# mini64se-v1_0_9-F4-2s.net
KiCad netlist of a schematic drawn in EAGLE
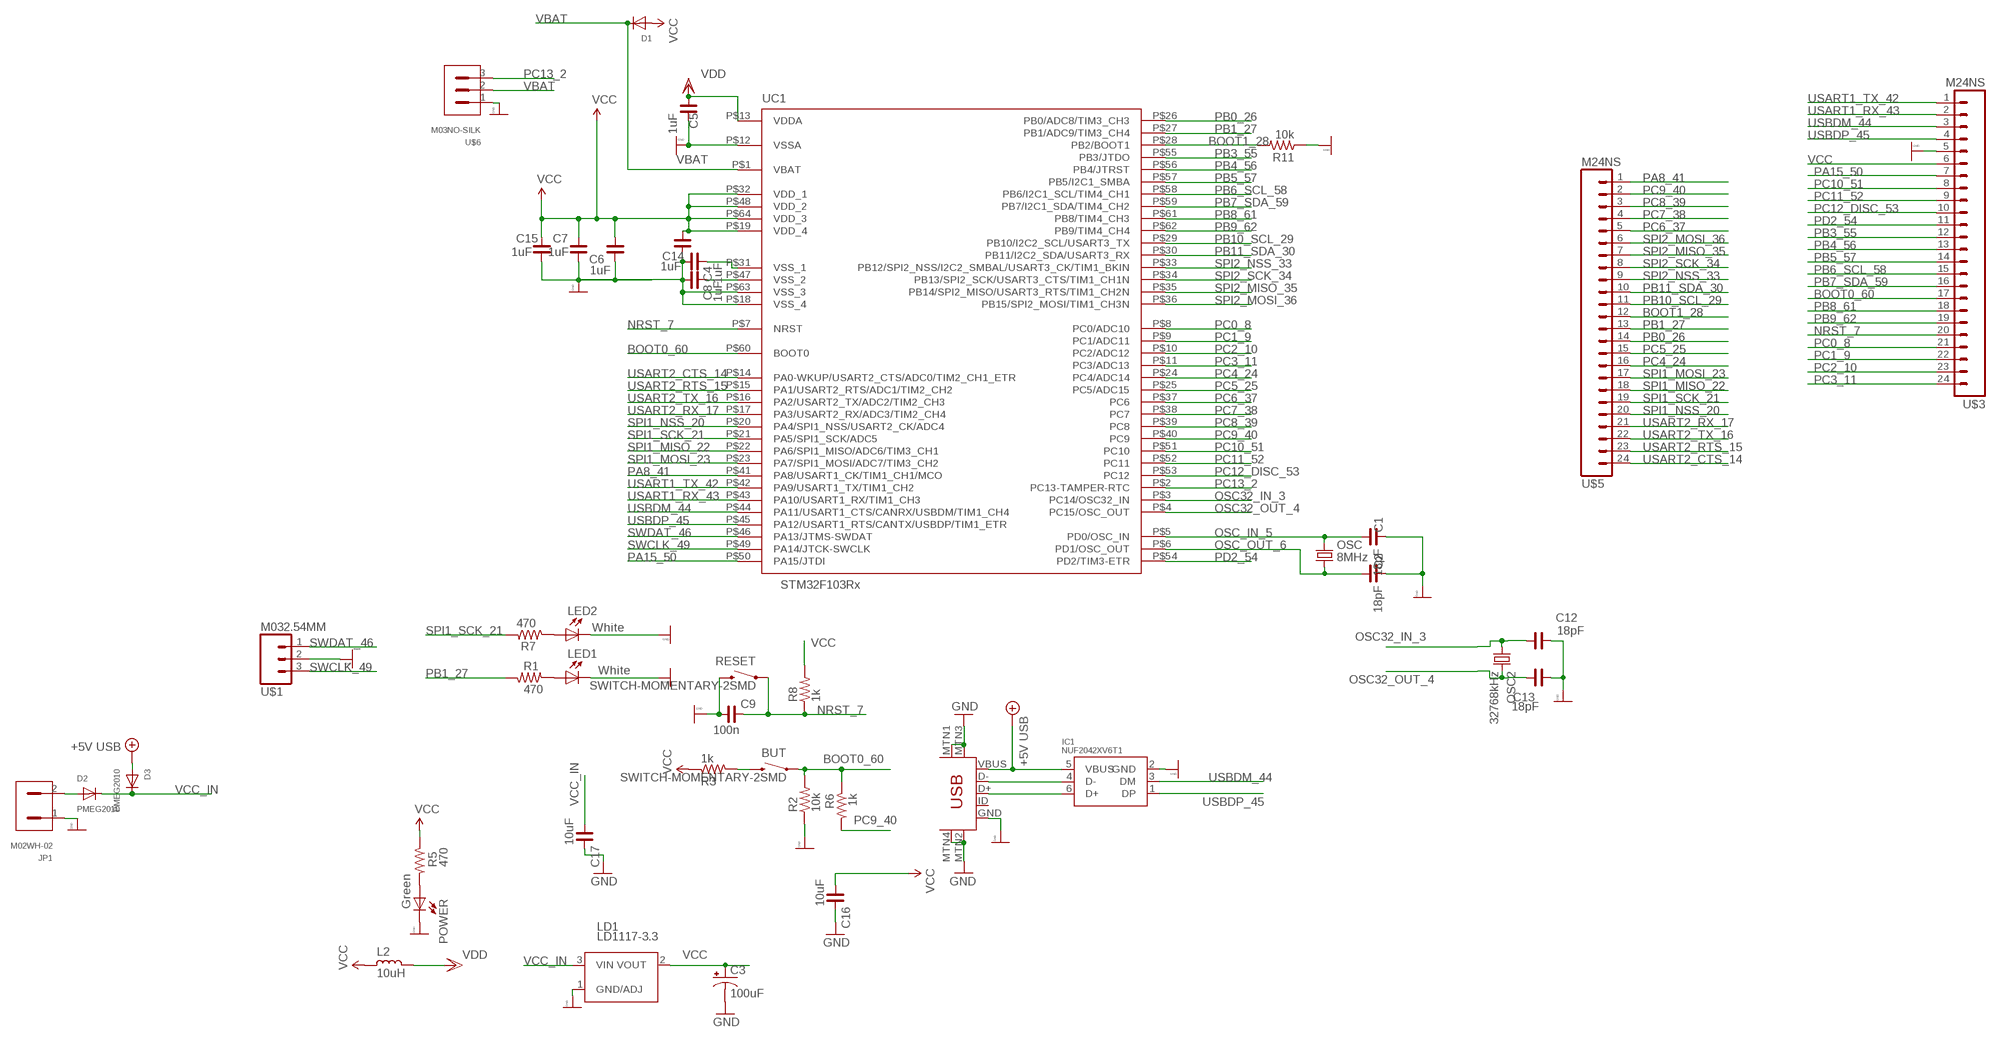
[diagram p0: schematic, sheet 1]

(export (version "E")
  (design (tool "Eeschema 10.0.6"))
  (components
    (comp (ref "BUT")
      (value "SWITCH-MOMENTARY-2SMD")
      (footprint "eagle-import:TACTILE_SWITCH_SMD")
      (libsource (lib "eagle-import") (part "SWITCH-MOMENTARY-2SMD"))
    )
    (comp (ref "C1")
      (value "18pF")
      (footprint "eagle-import:C0603")
      (libsource (lib "eagle-import") (part "C_0603"))
    )
    (comp (ref "C2")
      (value "18pF")
      (footprint "eagle-import:C0603")
      (libsource (lib "eagle-import") (part "C_0603"))
    )
    (comp (ref "C3")
      (value "100uF")
      (footprint "eagle-import:PANASONIC_C")
      (libsource (lib "eagle-import") (part "CAP_POLC"))
    )
    (comp (ref "C4")
      (value "1uF")
      (footprint "eagle-import:C0603")
      (libsource (lib "eagle-import") (part "C_0603"))
    )
    (comp (ref "C5")
      (value "1uF")
      (footprint "eagle-import:C0603")
      (libsource (lib "eagle-import") (part "C_0603"))
    )
    (comp (ref "C6")
      (value "1uF")
      (footprint "eagle-import:C0603")
      (libsource (lib "eagle-import") (part "C_0603"))
    )
    (comp (ref "C7")
      (value "1uF")
      (footprint "eagle-import:C0603")
      (libsource (lib "eagle-import") (part "C_0603"))
    )
    (comp (ref "C8")
      (value "1uF")
      (footprint "eagle-import:C0603")
      (libsource (lib "eagle-import") (part "C_0603"))
    )
    (comp (ref "C9")
      (value "100n")
      (footprint "eagle-import:C0603")
      (libsource (lib "eagle-import") (part "C_0603"))
    )
    (comp (ref "C12")
      (value "18pF")
      (footprint "eagle-import:C0603")
      (libsource (lib "eagle-import") (part "C_0603"))
    )
    (comp (ref "C13")
      (value "18pF")
      (footprint "eagle-import:C0603")
      (libsource (lib "eagle-import") (part "C_0603"))
    )
    (comp (ref "C14")
      (value "1uF")
      (footprint "eagle-import:C0603")
      (libsource (lib "eagle-import") (part "C_0603"))
    )
    (comp (ref "C15")
      (value "1uF")
      (footprint "eagle-import:C0603")
      (libsource (lib "eagle-import") (part "C_0603"))
    )
    (comp (ref "C16")
      (value "10uF")
      (footprint "eagle-import:C0805")
      (libsource (lib "eagle-import") (part "C_0805"))
    )
    (comp (ref "C17")
      (value "10uF")
      (footprint "eagle-import:C0805")
      (libsource (lib "eagle-import") (part "C_0805"))
    )
    (comp (ref "D1")
      (value "DIODESOD-123")
      (footprint "eagle-import:SOD-123")
      (libsource (lib "eagle-import") (part "DIODESOD-123"))
    )
    (comp (ref "D2")
      (value "PMEG2010")
      (footprint "eagle-import:SOD-123")
      (libsource (lib "eagle-import") (part "DIODESOD-123"))
    )
    (comp (ref "D3")
      (value "PMEG2010")
      (footprint "eagle-import:SOD-123")
      (libsource (lib "eagle-import") (part "DIODESOD-123"))
    )
    (comp (ref "IC1")
      (value "NUF2042XV6T1")
      (footprint "eagle-import:SOT-563")
      (libsource (lib "eagle-import") (part "NUF2042XV6T1"))
    )
    (comp (ref "JP1")
      (value "M02WH-02")
      (footprint "eagle-import:WH-02R")
      (libsource (lib "eagle-import") (part "M02WH-02"))
    )
    (comp (ref "L2")
      (value "10uH")
      (footprint "eagle-import:PM0603")
      (libsource (lib "eagle-import") (part "L_PM0603"))
    )
    (comp (ref "LD1")
      (value "LD1117-3.3")
      (footprint "eagle-import:SOT223")
      (libsource (lib "eagle-import") (part "LD1117SOT223"))
    )
    (comp (ref "LED1")
      (value "White")
      (footprint "eagle-import:CHIPLED_1206")
      (libsource (lib "eagle-import") (part "LEDCHIPLED_1206"))
    )
    (comp (ref "LED2")
      (value "White")
      (footprint "eagle-import:CHIPLED_1206")
      (libsource (lib "eagle-import") (part "LEDCHIPLED_1206"))
    )
    (comp (ref "OSC")
      (value "8MHz")
      (footprint "eagle-import:HC49U-V")
      (libsource (lib "eagle-import") (part "CRYSTALHC49UV"))
    )
    (comp (ref "OSC2")
      (value "32768kHz")
      (footprint "eagle-import:TC26H-M")
      (libsource (lib "eagle-import") (part "CRYSTALTC26HM"))
    )
    (comp (ref "POWER")
      (value "Green")
      (footprint "eagle-import:CHIP-LED0805")
      (libsource (lib "eagle-import") (part "LEDCHIP-LED0805"))
    )
    (comp (ref "R1")
      (value "470")
      (footprint "eagle-import:R0603")
      (libsource (lib "eagle-import") (part "R_0603"))
    )
    (comp (ref "R2")
      (value "10k")
      (footprint "eagle-import:R0603")
      (libsource (lib "eagle-import") (part "R_0603"))
    )
    (comp (ref "R3")
      (value "1k")
      (footprint "eagle-import:R0603")
      (libsource (lib "eagle-import") (part "R_0603"))
    )
    (comp (ref "R5")
      (value "470")
      (footprint "eagle-import:R0603")
      (libsource (lib "eagle-import") (part "R_0603"))
    )
    (comp (ref "R6")
      (value "1k")
      (footprint "eagle-import:R0603")
      (libsource (lib "eagle-import") (part "R_0603"))
    )
    (comp (ref "R7")
      (value "470")
      (footprint "eagle-import:R0603")
      (libsource (lib "eagle-import") (part "R_0603"))
    )
    (comp (ref "R8")
      (value "1k")
      (footprint "eagle-import:R0603")
      (libsource (lib "eagle-import") (part "R_0603"))
    )
    (comp (ref "R11")
      (value "10k")
      (footprint "eagle-import:R0603")
      (libsource (lib "eagle-import") (part "R_0603"))
    )
    (comp (ref "RESET")
      (value "SWITCH-MOMENTARY-2SMD")
      (footprint "eagle-import:TACTILE_SWITCH_SMD")
      (libsource (lib "eagle-import") (part "SWITCH-MOMENTARY-2SMD"))
    )
    (comp (ref "U$1")
      (value "M032.54MM")
      (footprint "eagle-import:1X03_NO_SILK")
      (libsource (lib "eagle-import") (part "M031X03_NO_SILK"))
    )
    (comp (ref "U$3")
      (value "M24NS")
      (footprint "eagle-import:1X24_NO_SILK")
      (libsource (lib "eagle-import") (part "M24NS"))
    )
    (comp (ref "U$5")
      (value "M24NS")
      (footprint "eagle-import:1X24_NO_SILK")
      (libsource (lib "eagle-import") (part "M24NS"))
    )
    (comp (ref "U$6")
      (value "M03NO-SILK")
      (footprint "eagle-import:1X03_NO_SILK")
      (libsource (lib "eagle-import") (part "M03NO-SILK"))
    )
    (comp (ref "UC1")
      (value "STM32F103Rx")
      (footprint "eagle-import:TQFP-10X10-64")
      (libsource (lib "eagle-import") (part "STM32F103"))
    )
    (comp (ref "USB")
      (value "USB-MINIB-5PIN")
      (footprint "eagle-import:USB-MINIB")
      (libsource (lib "eagle-import") (part "USB-MINIB-5PIN"))
    )
  )
  (nets
    (net (code "1") (name "+5V USB") (class "Default")
      (node (ref "D3") (pin "A") (pinfunction "A_A") (pintype "passive"))
      (node (ref "IC1") (pin "5") (pinfunction "VBUS_5") (pintype "bidirectional"))
      (node (ref "USB") (pin "VBUS") (pinfunction "VBUS_VBUS") (pintype "bidirectional"))
    )
    (net (code "2") (name "/BOOT0_60") (class "Default")
      (node (ref "BUT") (pin "1") (pinfunction "1_1") (pintype "passive"))
      (node (ref "R2") (pin "2") (pinfunction "2_2") (pintype "passive"))
      (node (ref "R6") (pin "1") (pinfunction "1_1") (pintype "passive"))
      (node (ref "U$3") (pin "17") (pinfunction "18_17") (pintype "passive"))
      (node (ref "UC1") (pin "P$60") (pinfunction "BOOT0_P$60") (pintype "bidirectional"))
    )
    (net (code "3") (name "/BOOT1_28") (class "Default")
      (node (ref "R11") (pin "2") (pinfunction "2_2") (pintype "passive"))
      (node (ref "U$5") (pin "12") (pinfunction "13_12") (pintype "passive"))
      (node (ref "UC1") (pin "P$28") (pinfunction "PB2/BOOT1_P$28") (pintype "bidirectional"))
    )
    (net (code "4") (name "/NRST_7") (class "Default")
      (node (ref "C9") (pin "2") (pinfunction "2_2") (pintype "passive"))
      (node (ref "R8") (pin "1") (pinfunction "1_1") (pintype "passive"))
      (node (ref "RESET") (pin "1") (pinfunction "1_1") (pintype "passive"))
      (node (ref "U$3") (pin "20") (pinfunction "21_20") (pintype "passive"))
      (node (ref "UC1") (pin "P$7") (pinfunction "NRST_P$7") (pintype "bidirectional"))
    )
    (net (code "5") (name "/OSC32_IN_3") (class "Default")
      (node (ref "C12") (pin "2") (pinfunction "2_2") (pintype "passive"))
      (node (ref "OSC2") (pin "1") (pinfunction "1_1") (pintype "passive"))
      (node (ref "UC1") (pin "P$3") (pinfunction "PC14/OSC32_IN_P$3") (pintype "bidirectional"))
    )
    (net (code "6") (name "/OSC32_OUT_4") (class "Default")
      (node (ref "C13") (pin "2") (pinfunction "2_2") (pintype "passive"))
      (node (ref "OSC2") (pin "2") (pinfunction "2_2") (pintype "passive"))
      (node (ref "UC1") (pin "P$4") (pinfunction "PC15/OSC_OUT_P$4") (pintype "bidirectional"))
    )
    (net (code "7") (name "/OSC_IN_5") (class "Default")
      (node (ref "C1") (pin "2") (pinfunction "2_2") (pintype "passive"))
      (node (ref "OSC") (pin "2") (pinfunction "2_2") (pintype "passive"))
      (node (ref "UC1") (pin "P$5") (pinfunction "PD0/OSC_IN_P$5") (pintype "bidirectional"))
    )
    (net (code "8") (name "/OSC_OUT_6") (class "Default")
      (node (ref "C2") (pin "2") (pinfunction "2_2") (pintype "passive"))
      (node (ref "OSC") (pin "1") (pinfunction "1_1") (pintype "passive"))
      (node (ref "UC1") (pin "P$6") (pinfunction "PD1/OSC_OUT_P$6") (pintype "bidirectional"))
    )
    (net (code "9") (name "/PA8_41") (class "Default")
      (node (ref "U$5") (pin "1") (pinfunction "2_1") (pintype "passive"))
      (node (ref "UC1") (pin "P$41") (pinfunction "PA8/USART1_CK/TIM1_CH1/MCO_P$41") (pintype "bidirectional"))
    )
    (net (code "10") (name "/PA15_50") (class "Default")
      (node (ref "U$3") (pin "7") (pinfunction "8_7") (pintype "passive"))
      (node (ref "UC1") (pin "P$50") (pinfunction "PA15/JTDI_P$50") (pintype "bidirectional"))
    )
    (net (code "11") (name "/PB0_26") (class "Default")
      (node (ref "U$5") (pin "14") (pinfunction "15_14") (pintype "passive"))
      (node (ref "UC1") (pin "P$26") (pinfunction "PB0/ADC8/TIM3_CH3_P$26") (pintype "bidirectional"))
    )
    (net (code "12") (name "/PB1_27") (class "Default")
      (node (ref "R1") (pin "2") (pinfunction "2_2") (pintype "passive"))
      (node (ref "U$5") (pin "13") (pinfunction "14_13") (pintype "passive"))
      (node (ref "UC1") (pin "P$27") (pinfunction "PB1/ADC9/TIM3_CH4_P$27") (pintype "bidirectional"))
    )
    (net (code "13") (name "/PB3_55") (class "Default")
      (node (ref "U$3") (pin "12") (pinfunction "13_12") (pintype "passive"))
      (node (ref "UC1") (pin "P$55") (pinfunction "PB3/JTDO_P$55") (pintype "bidirectional"))
    )
    (net (code "14") (name "/PB4_56") (class "Default")
      (node (ref "U$3") (pin "13") (pinfunction "14_13") (pintype "passive"))
      (node (ref "UC1") (pin "P$56") (pinfunction "PB4/JTRST_P$56") (pintype "bidirectional"))
    )
    (net (code "15") (name "/PB5_57") (class "Default")
      (node (ref "U$3") (pin "14") (pinfunction "15_14") (pintype "passive"))
      (node (ref "UC1") (pin "P$57") (pinfunction "PB5/I2C1_SMBA_P$57") (pintype "bidirectional"))
    )
    (net (code "16") (name "/PB6_SCL_58") (class "Default")
      (node (ref "U$3") (pin "15") (pinfunction "16_15") (pintype "passive"))
      (node (ref "UC1") (pin "P$58") (pinfunction "PB6/I2C1_SCL/TIM4_CH1_P$58") (pintype "bidirectional"))
    )
    (net (code "17") (name "/PB7_SDA_59") (class "Default")
      (node (ref "U$3") (pin "16") (pinfunction "17_16") (pintype "passive"))
      (node (ref "UC1") (pin "P$59") (pinfunction "PB7/I2C1_SDA/TIM4_CH2_P$59") (pintype "bidirectional"))
    )
    (net (code "18") (name "/PB8_61") (class "Default")
      (node (ref "U$3") (pin "18") (pinfunction "19_18") (pintype "passive"))
      (node (ref "UC1") (pin "P$61") (pinfunction "PB8/TIM4_CH3_P$61") (pintype "bidirectional"))
    )
    (net (code "19") (name "/PB9_62") (class "Default")
      (node (ref "U$3") (pin "19") (pinfunction "20_19") (pintype "passive"))
      (node (ref "UC1") (pin "P$62") (pinfunction "PB9/TIM4_CH4_P$62") (pintype "bidirectional"))
    )
    (net (code "20") (name "/PB10_SCL_29") (class "Default")
      (node (ref "U$5") (pin "11") (pinfunction "12_11") (pintype "passive"))
      (node (ref "UC1") (pin "P$29") (pinfunction "PB10/I2C2_SCL/USART3_TX_P$29") (pintype "bidirectional"))
    )
    (net (code "21") (name "/PB11_SDA_30") (class "Default")
      (node (ref "U$5") (pin "10") (pinfunction "11_10") (pintype "passive"))
      (node (ref "UC1") (pin "P$30") (pinfunction "PB11/I2C2_SDA/USART3_RX_P$30") (pintype "bidirectional"))
    )
    (net (code "22") (name "/PC0_8") (class "Default")
      (node (ref "U$3") (pin "21") (pinfunction "22_21") (pintype "passive"))
      (node (ref "UC1") (pin "P$8") (pinfunction "PC0/ADC10_P$8") (pintype "bidirectional"))
    )
    (net (code "23") (name "/PC1_9") (class "Default")
      (node (ref "U$3") (pin "22") (pinfunction "23_22") (pintype "passive"))
      (node (ref "UC1") (pin "P$9") (pinfunction "PC1/ADC11_P$9") (pintype "bidirectional"))
    )
    (net (code "24") (name "/PC2_10") (class "Default")
      (node (ref "U$3") (pin "23") (pinfunction "24_23") (pintype "passive"))
      (node (ref "UC1") (pin "P$10") (pinfunction "PC2/ADC12_P$10") (pintype "bidirectional"))
    )
    (net (code "25") (name "/PC3_11") (class "Default")
      (node (ref "U$3") (pin "24") (pinfunction "25_24") (pintype "passive"))
      (node (ref "UC1") (pin "P$11") (pinfunction "PC3/ADC13_P$11") (pintype "bidirectional"))
    )
    (net (code "26") (name "/PC4_24") (class "Default")
      (node (ref "U$5") (pin "16") (pinfunction "17_16") (pintype "passive"))
      (node (ref "UC1") (pin "P$24") (pinfunction "PC4/ADC14_P$24") (pintype "bidirectional"))
    )
    (net (code "27") (name "/PC5_25") (class "Default")
      (node (ref "U$5") (pin "15") (pinfunction "16_15") (pintype "passive"))
      (node (ref "UC1") (pin "P$25") (pinfunction "PC5/ADC15_P$25") (pintype "bidirectional"))
    )
    (net (code "28") (name "/PC6_37") (class "Default")
      (node (ref "U$5") (pin "5") (pinfunction "6_5") (pintype "passive"))
      (node (ref "UC1") (pin "P$37") (pinfunction "PC6_P$37") (pintype "bidirectional"))
    )
    (net (code "29") (name "/PC7_38") (class "Default")
      (node (ref "U$5") (pin "4") (pinfunction "5_4") (pintype "passive"))
      (node (ref "UC1") (pin "P$38") (pinfunction "PC7_P$38") (pintype "bidirectional"))
    )
    (net (code "30") (name "/PC8_39") (class "Default")
      (node (ref "U$5") (pin "3") (pinfunction "4_3") (pintype "passive"))
      (node (ref "UC1") (pin "P$39") (pinfunction "PC8_P$39") (pintype "bidirectional"))
    )
    (net (code "31") (name "/PC9_40") (class "Default")
      (node (ref "R6") (pin "2") (pinfunction "2_2") (pintype "passive"))
      (node (ref "U$5") (pin "2") (pinfunction "3_2") (pintype "passive"))
      (node (ref "UC1") (pin "P$40") (pinfunction "PC9_P$40") (pintype "bidirectional"))
    )
    (net (code "32") (name "/PC10_51") (class "Default")
      (node (ref "U$3") (pin "8") (pinfunction "9_8") (pintype "passive"))
      (node (ref "UC1") (pin "P$51") (pinfunction "PC10_P$51") (pintype "bidirectional"))
    )
    (net (code "33") (name "/PC11_52") (class "Default")
      (node (ref "U$3") (pin "9") (pinfunction "10_9") (pintype "passive"))
      (node (ref "UC1") (pin "P$52") (pinfunction "PC11_P$52") (pintype "bidirectional"))
    )
    (net (code "34") (name "/PC12_DISC_53") (class "Default")
      (node (ref "U$3") (pin "10") (pinfunction "11_10") (pintype "passive"))
      (node (ref "UC1") (pin "P$53") (pinfunction "PC12_P$53") (pintype "bidirectional"))
    )
    (net (code "35") (name "/PC13_2") (class "Default")
      (node (ref "U$6") (pin "3") (pinfunction "3_3") (pintype "bidirectional"))
      (node (ref "UC1") (pin "P$2") (pinfunction "PC13-TAMPER-RTC_P$2") (pintype "bidirectional"))
    )
    (net (code "36") (name "/PD2_54") (class "Default")
      (node (ref "U$3") (pin "11") (pinfunction "12_11") (pintype "passive"))
      (node (ref "UC1") (pin "P$54") (pinfunction "PD2/TIM3-ETR_P$54") (pintype "bidirectional"))
    )
    (net (code "37") (name "/SPI1_MISO_22") (class "Default")
      (node (ref "U$5") (pin "18") (pinfunction "19_18") (pintype "passive"))
      (node (ref "UC1") (pin "P$22") (pinfunction "PA6/SPI1_MISO/ADC6/TIM3_CH1_P$22") (pintype "bidirectional"))
    )
    (net (code "38") (name "/SPI1_MOSI_23") (class "Default")
      (node (ref "U$5") (pin "17") (pinfunction "18_17") (pintype "passive"))
      (node (ref "UC1") (pin "P$23") (pinfunction "PA7/SPI1_MOSI/ADC7/TIM3_CH2_P$23") (pintype "bidirectional"))
    )
    (net (code "39") (name "/SPI1_NSS_20") (class "Default")
      (node (ref "U$5") (pin "20") (pinfunction "21_20") (pintype "passive"))
      (node (ref "UC1") (pin "P$20") (pinfunction "PA4/SPI1_NSS/USART2_CK/ADC4_P$20") (pintype "bidirectional"))
    )
    (net (code "40") (name "/SPI1_SCK_21") (class "Default")
      (node (ref "R7") (pin "1") (pinfunction "1_1") (pintype "passive"))
      (node (ref "U$5") (pin "19") (pinfunction "20_19") (pintype "passive"))
      (node (ref "UC1") (pin "P$21") (pinfunction "PA5/SPI1_SCK/ADC5_P$21") (pintype "bidirectional"))
    )
    (net (code "41") (name "/SPI2_MISO_35") (class "Default")
      (node (ref "U$5") (pin "7") (pinfunction "8_7") (pintype "passive"))
      (node (ref "UC1") (pin "P$35") (pinfunction "PB14/SPI2_MISO/USART3_RTS/TIM1_CH2N_P$35") (pintype "bidirectional"))
    )
    (net (code "42") (name "/SPI2_MOSI_36") (class "Default")
      (node (ref "U$5") (pin "6") (pinfunction "7_6") (pintype "passive"))
      (node (ref "UC1") (pin "P$36") (pinfunction "PB15/SPI2_MOSI/TIM1_CH3N_P$36") (pintype "bidirectional"))
    )
    (net (code "43") (name "/SPI2_NSS_33") (class "Default")
      (node (ref "U$5") (pin "9") (pinfunction "10_9") (pintype "passive"))
      (node (ref "UC1") (pin "P$33") (pinfunction "PB12/SPI2_NSS/I2C2_SMBAL/USART3_CK/TIM1_BKIN_P$33") (pintype "bidirectional"))
    )
    (net (code "44") (name "/SPI2_SCK_34") (class "Default")
      (node (ref "U$5") (pin "8") (pinfunction "9_8") (pintype "passive"))
      (node (ref "UC1") (pin "P$34") (pinfunction "PB13/SPI2_SCK/USART3_CTS/TIM1_CH1N_P$34") (pintype "bidirectional"))
    )
    (net (code "45") (name "/SWCLK_49") (class "Default")
      (node (ref "U$1") (pin "3") (pinfunction "3_3") (pintype "passive"))
      (node (ref "UC1") (pin "P$49") (pinfunction "PA14/JTCK-SWCLK_P$49") (pintype "bidirectional"))
    )
    (net (code "46") (name "/SWDAT_46") (class "Default")
      (node (ref "U$1") (pin "1") (pinfunction "1_1") (pintype "passive"))
      (node (ref "UC1") (pin "P$46") (pinfunction "PA13/JTMS-SWDAT_P$46") (pintype "bidirectional"))
    )
    (net (code "47") (name "/USART1_RX_43") (class "Default")
      (node (ref "U$3") (pin "2") (pinfunction "3_2") (pintype "passive"))
      (node (ref "UC1") (pin "P$43") (pinfunction "PA10/USART1_RX/TIM1_CH3_P$43") (pintype "bidirectional"))
    )
    (net (code "48") (name "/USART1_TX_42") (class "Default")
      (node (ref "U$3") (pin "1") (pinfunction "2_1") (pintype "passive"))
      (node (ref "UC1") (pin "P$42") (pinfunction "PA9/USART1_TX/TIM1_CH2_P$42") (pintype "bidirectional"))
    )
    (net (code "49") (name "/USART2_CTS_14") (class "Default")
      (node (ref "U$5") (pin "24") (pinfunction "25_24") (pintype "passive"))
      (node (ref "UC1") (pin "P$14") (pinfunction "PA0-WKUP/USART2_CTS/ADC0/TIM2_CH1_ETR_P$14") (pintype "bidirectional"))
    )
    (net (code "50") (name "/USART2_RTS_15") (class "Default")
      (node (ref "U$5") (pin "23") (pinfunction "24_23") (pintype "passive"))
      (node (ref "UC1") (pin "P$15") (pinfunction "PA1/USART2_RTS/ADC1/TIM2_CH2_P$15") (pintype "bidirectional"))
    )
    (net (code "51") (name "/USART2_RX_17") (class "Default")
      (node (ref "U$5") (pin "21") (pinfunction "22_21") (pintype "passive"))
      (node (ref "UC1") (pin "P$17") (pinfunction "PA3/USART2_RX/ADC3/TIM2_CH4_P$17") (pintype "bidirectional"))
    )
    (net (code "52") (name "/USART2_TX_16") (class "Default")
      (node (ref "U$5") (pin "22") (pinfunction "23_22") (pintype "passive"))
      (node (ref "UC1") (pin "P$16") (pinfunction "PA2/USART2_TX/ADC2/TIM2_CH3_P$16") (pintype "bidirectional"))
    )
    (net (code "53") (name "/USBDM_44") (class "Default")
      (node (ref "IC1") (pin "3") (pinfunction "DM_3") (pintype "bidirectional"))
      (node (ref "U$3") (pin "3") (pinfunction "4_3") (pintype "passive"))
      (node (ref "UC1") (pin "P$44") (pinfunction "PA11/USART1_CTS/CANRX/USBDM/TIM1_CH4_P$44") (pintype "bidirectional"))
    )
    (net (code "54") (name "/USBDP_45") (class "Default")
      (node (ref "IC1") (pin "1") (pinfunction "DP_1") (pintype "bidirectional"))
      (node (ref "U$3") (pin "4") (pinfunction "5_4") (pintype "passive"))
      (node (ref "UC1") (pin "P$45") (pinfunction "PA12/USART1_RTS/CANTX/USBDP/TIM1_ETR_P$45") (pintype "bidirectional"))
    )
    (net (code "55") (name "/VBAT") (class "Default")
      (node (ref "D1") (pin "C") (pinfunction "C_C") (pintype "passive"))
      (node (ref "U$6") (pin "2") (pinfunction "2_2") (pintype "bidirectional"))
      (node (ref "UC1") (pin "P$1") (pinfunction "VBAT_P$1") (pintype "power_in"))
    )
    (net (code "56") (name "/VCC_IN") (class "Default")
      (node (ref "C17") (pin "1") (pinfunction "1_1") (pintype "passive"))
      (node (ref "D2") (pin "C") (pinfunction "C_C") (pintype "passive"))
      (node (ref "D3") (pin "C") (pinfunction "C_C") (pintype "passive"))
      (node (ref "LD1") (pin "3") (pinfunction "VIN_3") (pintype "bidirectional"))
    )
    (net (code "57") (name "GND") (class "Default")
      (node (ref "C1") (pin "1") (pinfunction "1_1") (pintype "passive"))
      (node (ref "C12") (pin "1") (pinfunction "1_1") (pintype "passive"))
      (node (ref "C13") (pin "1") (pinfunction "1_1") (pintype "passive"))
      (node (ref "C14") (pin "1") (pinfunction "1_1") (pintype "passive"))
      (node (ref "C15") (pin "1") (pinfunction "1_1") (pintype "passive"))
      (node (ref "C16") (pin "2") (pinfunction "2_2") (pintype "passive"))
      (node (ref "C17") (pin "2") (pinfunction "2_2") (pintype "passive"))
      (node (ref "C2") (pin "1") (pinfunction "1_1") (pintype "passive"))
      (node (ref "C3") (pin "-") (pinfunction "-_-") (pintype "passive"))
      (node (ref "C4") (pin "2") (pinfunction "2_2") (pintype "passive"))
      (node (ref "C5") (pin "1") (pinfunction "1_1") (pintype "passive"))
      (node (ref "C6") (pin "1") (pinfunction "1_1") (pintype "passive"))
      (node (ref "C7") (pin "1") (pinfunction "1_1") (pintype "passive"))
      (node (ref "C8") (pin "2") (pinfunction "2_2") (pintype "passive"))
      (node (ref "C9") (pin "1") (pinfunction "1_1") (pintype "passive"))
      (node (ref "IC1") (pin "2") (pinfunction "GND_2") (pintype "bidirectional"))
      (node (ref "JP1") (pin "1") (pinfunction "P$1_1") (pintype "bidirectional"))
      (node (ref "LD1") (pin "1") (pinfunction "GND/ADJ_1") (pintype "bidirectional"))
      (node (ref "LED1") (pin "C") (pinfunction "C_C") (pintype "passive"))
      (node (ref "LED2") (pin "C") (pinfunction "C_C") (pintype "passive"))
      (node (ref "POWER") (pin "C") (pinfunction "C_C") (pintype "passive"))
      (node (ref "R11") (pin "1") (pinfunction "1_1") (pintype "passive"))
      (node (ref "R2") (pin "1") (pinfunction "1_1") (pintype "passive"))
      (node (ref "RESET") (pin "3") (pinfunction "2_3") (pintype "passive"))
      (node (ref "U$1") (pin "2") (pinfunction "2_2") (pintype "passive"))
      (node (ref "U$3") (pin "5") (pinfunction "6_5") (pintype "passive"))
      (node (ref "U$6") (pin "1") (pinfunction "1_1") (pintype "bidirectional"))
      (node (ref "UC1") (pin "P$12") (pinfunction "VSSA_P$12") (pintype "power_in"))
      (node (ref "UC1") (pin "P$18") (pinfunction "VSS_4_P$18") (pintype "power_in"))
      (node (ref "UC1") (pin "P$63") (pinfunction "VSS_3_P$63") (pintype "power_in"))
      (node (ref "USB") (pin "GND") (pinfunction "GND_GND") (pintype "bidirectional"))
      (node (ref "USB") (pin "MTN1") (pinfunction "MTN2_MTN1") (pintype "bidirectional"))
      (node (ref "USB") (pin "MTN2") (pinfunction "MTN3_MTN2") (pintype "bidirectional"))
      (node (ref "USB") (pin "MTN3") (pinfunction "MTN1_MTN3") (pintype "bidirectional"))
      (node (ref "USB") (pin "MTN4") (pinfunction "MTN4_MTN4") (pintype "bidirectional"))
    )
    (net (code "58") (name "Net-(BUT-2)") (class "Default")
      (node (ref "BUT") (pin "3") (pinfunction "2_3") (pintype "passive"))
      (node (ref "R3") (pin "2") (pinfunction "2_2") (pintype "passive"))
    )
    (net (code "59") (name "Net-(IC1-D+)") (class "Default")
      (node (ref "IC1") (pin "6") (pinfunction "D+_6") (pintype "bidirectional"))
      (node (ref "USB") (pin "D+") (pinfunction "D+_D+") (pintype "bidirectional"))
    )
    (net (code "60") (name "Net-(IC1-D-)") (class "Default")
      (node (ref "IC1") (pin "4") (pinfunction "D-_4") (pintype "bidirectional"))
      (node (ref "USB") (pin "D-") (pinfunction "D-_D-") (pintype "bidirectional"))
    )
    (net (code "61") (name "Net-(JP1-P$2)") (class "Default")
      (node (ref "D2") (pin "A") (pinfunction "A_A") (pintype "passive"))
      (node (ref "JP1") (pin "2") (pinfunction "P$2_2") (pintype "bidirectional"))
    )
    (net (code "62") (name "Net-(LED1-PadA)") (class "Default")
      (node (ref "LED1") (pin "A") (pinfunction "A_A") (pintype "passive"))
      (node (ref "R1") (pin "1") (pinfunction "1_1") (pintype "passive"))
    )
    (net (code "63") (name "Net-(LED2-PadA)") (class "Default")
      (node (ref "LED2") (pin "A") (pinfunction "A_A") (pintype "passive"))
      (node (ref "R7") (pin "2") (pinfunction "2_2") (pintype "passive"))
    )
    (net (code "64") (name "Net-(POWER-PadA)") (class "Default")
      (node (ref "POWER") (pin "A") (pinfunction "A_A") (pintype "passive"))
      (node (ref "R5") (pin "2") (pinfunction "2_2") (pintype "passive"))
    )
    (net (code "65") (name "Net-(UC1-VSS_1)") (class "Default")
      (node (ref "C4") (pin "1") (pinfunction "1_1") (pintype "passive"))
      (node (ref "UC1") (pin "P$31") (pinfunction "VSS_1_P$31") (pintype "power_in"))
    )
    (net (code "66") (name "Net-(UC1-VSS_2)") (class "Default")
      (node (ref "C8") (pin "1") (pinfunction "1_1") (pintype "passive"))
      (node (ref "UC1") (pin "P$47") (pinfunction "VSS_2_P$47") (pintype "power_in"))
    )
    (net (code "67") (name "VCC") (class "Default")
      (node (ref "C14") (pin "2") (pinfunction "2_2") (pintype "passive"))
      (node (ref "C15") (pin "2") (pinfunction "2_2") (pintype "passive"))
      (node (ref "C16") (pin "1") (pinfunction "1_1") (pintype "passive"))
      (node (ref "C3") (pin "+") (pinfunction "+_+") (pintype "passive"))
      (node (ref "C6") (pin "2") (pinfunction "2_2") (pintype "passive"))
      (node (ref "C7") (pin "2") (pinfunction "2_2") (pintype "passive"))
      (node (ref "D1") (pin "A") (pinfunction "A_A") (pintype "passive"))
      (node (ref "L2") (pin "2") (pinfunction "2_2") (pintype "passive"))
      (node (ref "LD1") (pin "2") (pinfunction "VOUT_2") (pintype "bidirectional"))
      (node (ref "R3") (pin "1") (pinfunction "1_1") (pintype "passive"))
      (node (ref "R5") (pin "1") (pinfunction "1_1") (pintype "passive"))
      (node (ref "R8") (pin "2") (pinfunction "2_2") (pintype "passive"))
      (node (ref "U$3") (pin "6") (pinfunction "7_6") (pintype "passive"))
      (node (ref "UC1") (pin "P$19") (pinfunction "VDD_4_P$19") (pintype "power_in"))
      (node (ref "UC1") (pin "P$32") (pinfunction "VDD_1_P$32") (pintype "power_in"))
      (node (ref "UC1") (pin "P$48") (pinfunction "VDD_2_P$48") (pintype "power_in"))
      (node (ref "UC1") (pin "P$64") (pinfunction "VDD_3_P$64") (pintype "power_in"))
    )
    (net (code "68") (name "VDD") (class "Default")
      (node (ref "C5") (pin "2") (pinfunction "2_2") (pintype "passive"))
      (node (ref "L2") (pin "1") (pinfunction "1_1") (pintype "passive"))
      (node (ref "UC1") (pin "P$13") (pinfunction "VDDA_P$13") (pintype "power_in"))
    )
    (net (code "69") (name "unconnected-(USB-PadID)") (class "Default")
      (node (ref "USB") (pin "ID") (pinfunction "ID_ID") (pintype "bidirectional"))
    )
  )
)
